# SCH_STM32F103C8T6.net
KiCad netlist of a schematic drawn in Altium Designer
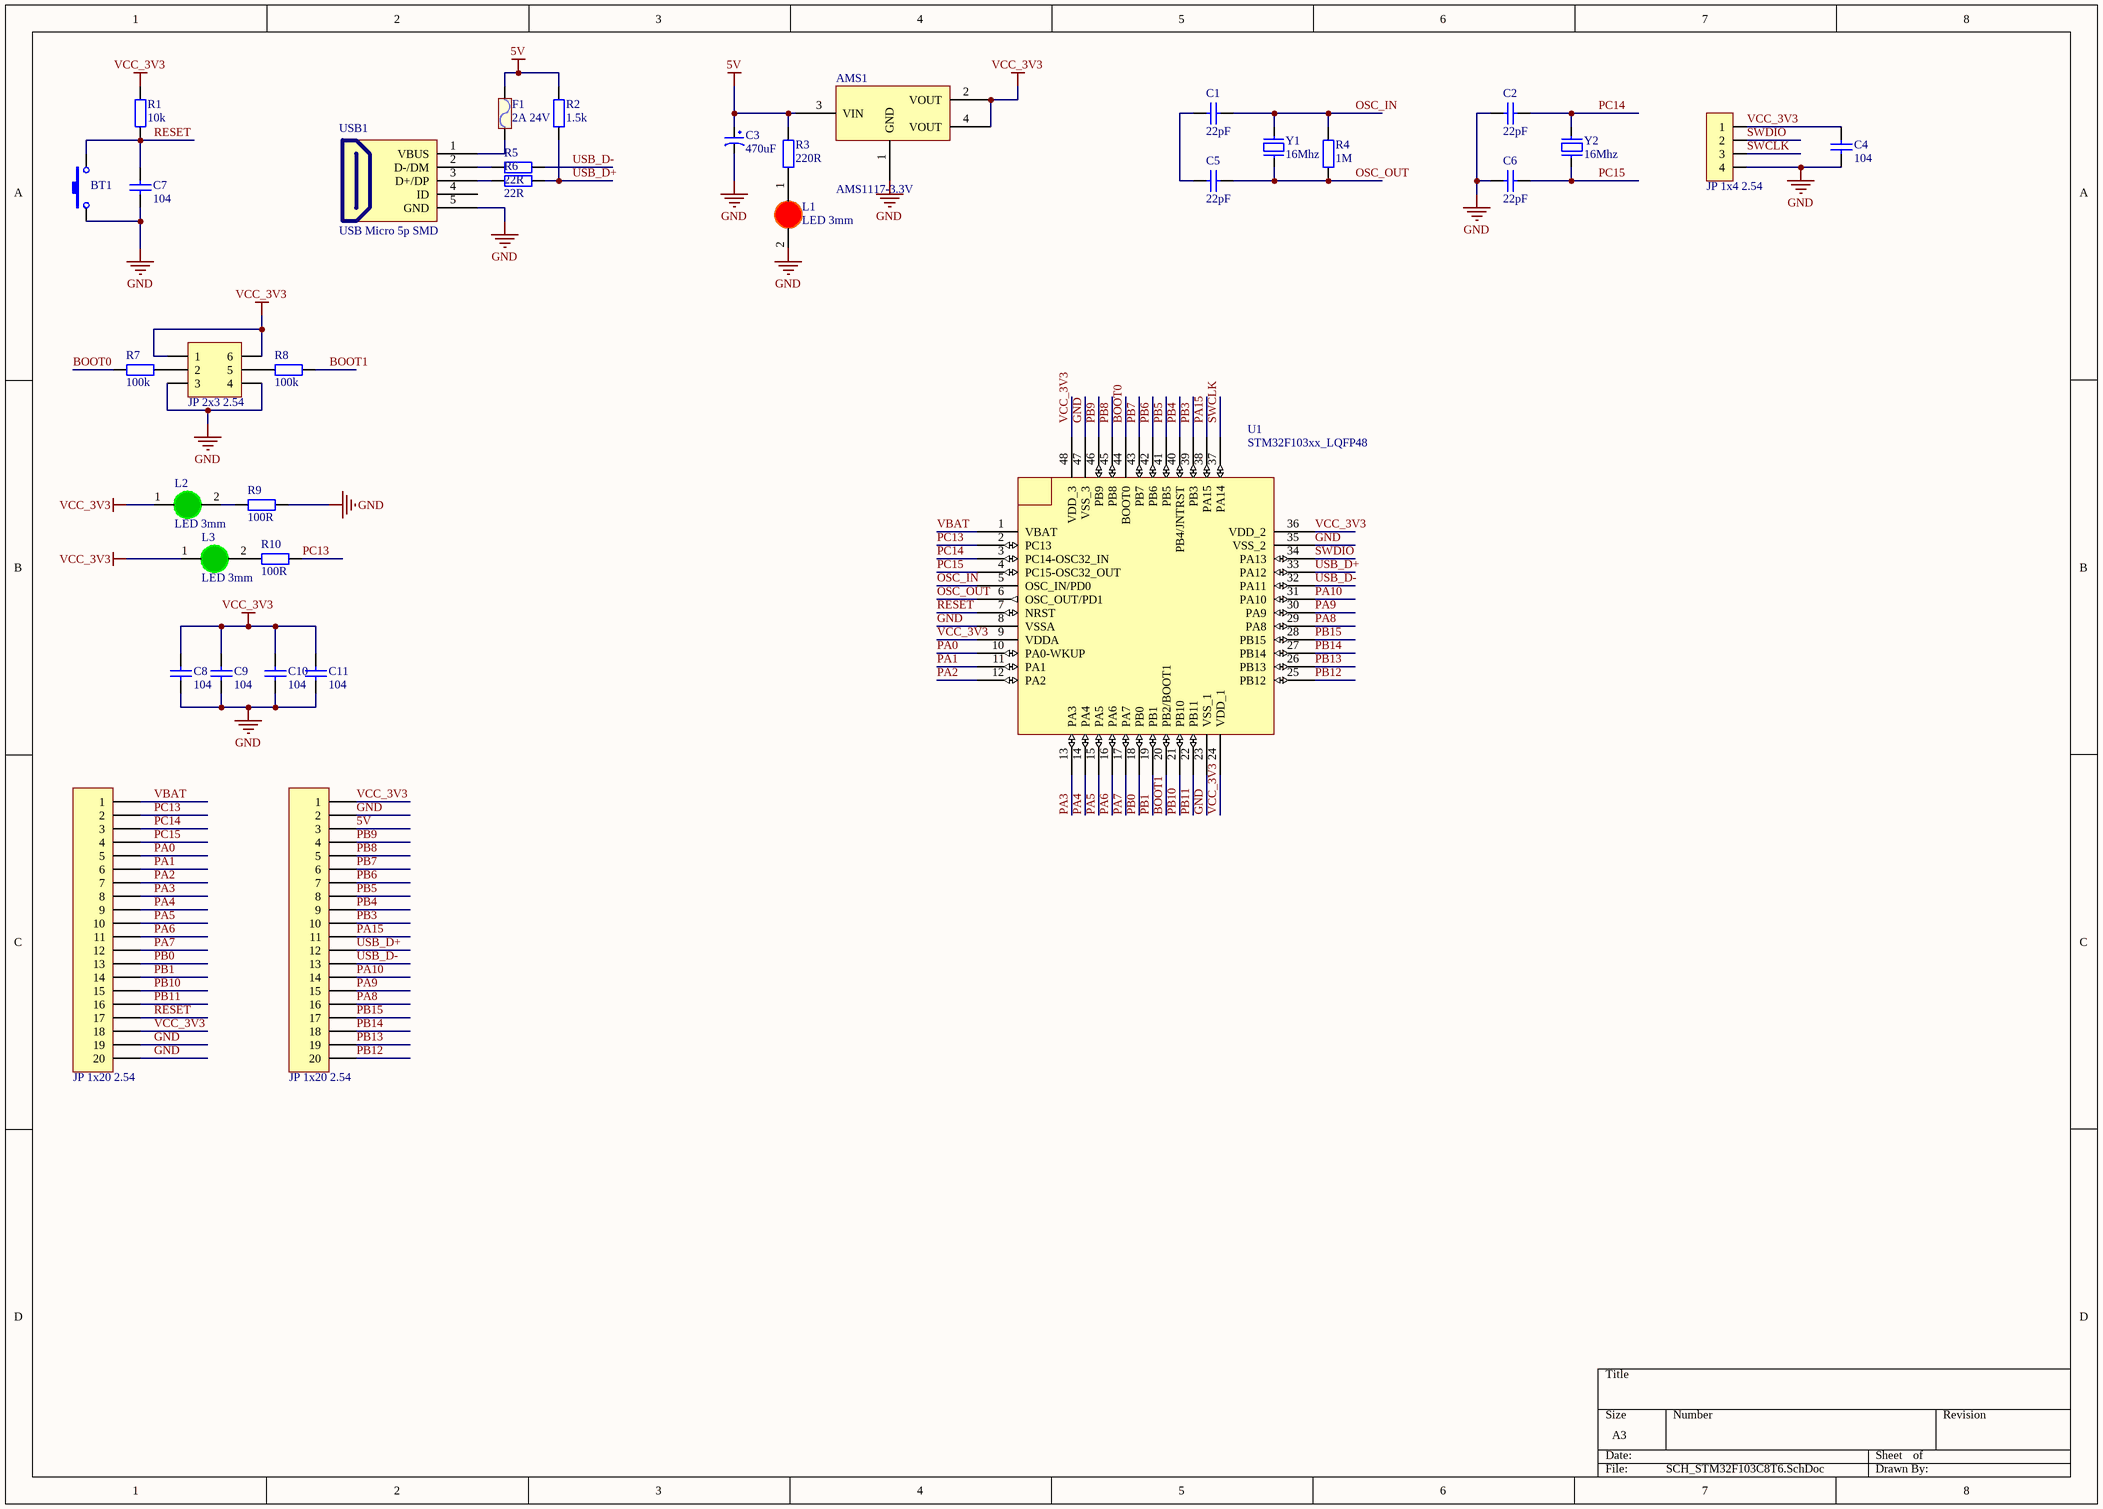
[diagram p0: SCH_STM32F103C8T6.SchDoc]

(export (version "E")
  (design (tool "Eeschema 10.0.6"))
  (components
    (comp (ref "AMS1")
      (value "AMS1117-3.3V")
      (footprint "SOT223")
      (description "Dán")
      (libsource (lib "Altium_Lib_by_KhueNguyenCreator") (part "AMS1117 SMD"))
    )
    (comp (ref "BT1")
      (value "Nut Nhan 2 Chan SMD 3x6x2.5")
      (footprint "Nut Nhan 2 Chan SMD 3x6x2.5")
      (libsource (lib "Altium_Lib_by_KhueNguyenCreator") (part "Nut Nhan 2 Chan SMD 3x6x2.5"))
    )
    (comp (ref "C1")
      (value "22pF")
      (footprint "tu 0805")
      (description "Dán")
      (libsource (lib "Altium_Lib_by_KhueNguyenCreator") (part "Tu 0805 22pF 50V 10%"))
    )
    (comp (ref "C2")
      (value "22pF")
      (footprint "tu 0805")
      (description "Dán")
      (libsource (lib "Altium_Lib_by_KhueNguyenCreator") (part "Tu 0805 22pF 50V 10%"))
    )
    (comp (ref "C3")
      (value "470uF")
      (footprint "tu hoa 8mm")
      (description "Cắm")
      (libsource (lib "Altium_Lib_by_KhueNguyenCreator") (part "Tu Hoa 470uF 16V 8x11"))
    )
    (comp (ref "C4")
      (value "104")
      (footprint "tu gom")
      (description "Cắm")
      (libsource (lib "Altium_Lib_by_KhueNguyenCreator") (part "Tu gom 104 50V"))
    )
    (comp (ref "C5")
      (value "22pF")
      (footprint "tu 0805")
      (description "Dán")
      (libsource (lib "Altium_Lib_by_KhueNguyenCreator") (part "Tu 0805 22pF 50V 10%"))
    )
    (comp (ref "C6")
      (value "22pF")
      (footprint "tu 0805")
      (description "Dán")
      (libsource (lib "Altium_Lib_by_KhueNguyenCreator") (part "Tu 0805 22pF 50V 10%"))
    )
    (comp (ref "C7")
      (value "104")
      (footprint "tu 0805")
      (description "Dán")
      (libsource (lib "Altium_Lib_by_KhueNguyenCreator") (part "Tu 0805 104 50V 10%"))
    )
    (comp (ref "C8")
      (value "104")
      (footprint "tu 0805")
      (description "Dán")
      (libsource (lib "Altium_Lib_by_KhueNguyenCreator") (part "Tu 0805 104 50V 10%"))
    )
    (comp (ref "C9")
      (value "104")
      (footprint "tu 0805")
      (description "Dán")
      (libsource (lib "Altium_Lib_by_KhueNguyenCreator") (part "Tu 0805 104 50V 10%"))
    )
    (comp (ref "C10")
      (value "104")
      (footprint "tu 0805")
      (description "Dán")
      (libsource (lib "Altium_Lib_by_KhueNguyenCreator") (part "Tu 0805 104 50V 10%"))
    )
    (comp (ref "C11")
      (value "104")
      (footprint "tu 0805")
      (description "Dán")
      (libsource (lib "Altium_Lib_by_KhueNguyenCreator") (part "Tu 0805 104 50V 10%"))
    )
    (comp (ref "F1")
      (value "2A 24V")
      (footprint "Cau chi tu phuc hoi 2A 24V SMD1812")
      (description "2A 24V SMD1812")
      (libsource (lib "Altium_Lib_by_KhueNguyenCreator") (part "Cau chi tu phuc hoi 2A 24V SMD1812"))
    )
    (comp (ref "JP1")
      (value "JP 1x4 2.54")
      (footprint "JP 1x4 DC")
      (description "Cắm")
      (libsource (lib "Altium_Lib_by_KhueNguyenCreator") (part "JP 1x4 2.54 Duc Cong"))
    )
    (comp (ref "JP2")
      (value "JP 2x3 2.54")
      (footprint "JP 2x3 DT")
      (description "Cắm")
      (libsource (lib "Altium_Lib_by_KhueNguyenCreator") (part "JP 2x3 2.54 Duc Thang"))
    )
    (comp (ref "JP3")
      (value "JP 1x20 2.54")
      (footprint "JP 1x20 DT")
      (description "Cắm")
      (libsource (lib "Altium_Lib_by_KhueNguyenCreator") (part "JP 1x20 2.54 Duc Thang"))
    )
    (comp (ref "JP4")
      (value "JP 1x20 2.54")
      (footprint "JP 1x20 DT")
      (description "Cắm")
      (libsource (lib "Altium_Lib_by_KhueNguyenCreator") (part "JP 1x20 2.54 Duc Thang"))
    )
    (comp (ref "L1")
      (value "LED 3mm")
      (footprint "LED-3MM-RED")
      (description "Cắm")
      (libsource (lib "Altium_Lib_by_KhueNguyenCreator") (part "LED 3mm Do"))
    )
    (comp (ref "L2")
      (value "LED 3mm")
      (footprint "LED-3MM-GREEN")
      (description "Cắm")
      (libsource (lib "Altium_Lib_by_KhueNguyenCreator") (part "LED 3mm Xanh La"))
    )
    (comp (ref "L3")
      (value "LED 3mm")
      (footprint "LED-3MM-GREEN")
      (description "Cắm")
      (libsource (lib "Altium_Lib_by_KhueNguyenCreator") (part "LED 3mm Xanh La"))
    )
    (comp (ref "R1")
      (value "10k")
      (footprint "tro smd 0805")
      (description "Dán")
      (libsource (lib "Altium_Lib_by_KhueNguyenCreator") (part "Tro 0805 1% 10k"))
    )
    (comp (ref "R2")
      (value "1.5k")
      (footprint "tro smd 0805")
      (description "Dán")
      (libsource (lib "Altium_Lib_by_KhueNguyenCreator") (part "Tro 0805 5% 1.5k"))
    )
    (comp (ref "R3")
      (value "220R")
      (footprint "tro smd 0805")
      (description "Dán")
      (libsource (lib "Altium_Lib_by_KhueNguyenCreator") (part "Tro 0805 5% 220R"))
    )
    (comp (ref "R4")
      (value "1M")
      (footprint "tro smd 0805")
      (description "Dán")
      (libsource (lib "Altium_Lib_by_KhueNguyenCreator") (part "Tro 0805 5% 1M"))
    )
    (comp (ref "R5")
      (value "22R")
      (footprint "tro smd 0805")
      (description "Dán")
      (libsource (lib "Altium_Lib_by_KhueNguyenCreator") (part "Tro 0805 5% 22R"))
    )
    (comp (ref "R6")
      (value "22R")
      (footprint "tro smd 0805")
      (description "Dán")
      (libsource (lib "Altium_Lib_by_KhueNguyenCreator") (part "Tro 0805 5% 22R"))
    )
    (comp (ref "R7")
      (value "100k")
      (footprint "tro smd 0603")
      (description "Dán")
      (libsource (lib "Altium_Lib_by_KhueNguyenCreator") (part "Tro 0603 5% 100k"))
    )
    (comp (ref "R8")
      (value "100k")
      (footprint "tro smd 0603")
      (description "Dán")
      (libsource (lib "Altium_Lib_by_KhueNguyenCreator") (part "Tro 0603 5% 100k"))
    )
    (comp (ref "R9")
      (value "100R")
      (footprint "tro smd 0805")
      (description "Dán")
      (libsource (lib "Altium_Lib_by_KhueNguyenCreator") (part "Tro 0805 5% 100R"))
    )
    (comp (ref "R10")
      (value "100R")
      (footprint "tro smd 0805")
      (description "Dán")
      (libsource (lib "Altium_Lib_by_KhueNguyenCreator") (part "Tro 0805 5% 100R"))
    )
    (comp (ref "U1")
      (value "STM32F103xx_LQFP48")
      (footprint "STM32_LQPF48")
      (fields (field (name "PUBLISHER") "Altium Limited"))
      (libsource (lib "Altium_Lib_by_KhueNguyenCreator") (part "STM32F103xx_LQFP48"))
    )
    (comp (ref "USB1")
      (value "USB Micro 5p SMD")
      (footprint "USB Micro 5p SMD")
      (description "USB Type B")
      (libsource (lib "Altium_Lib_by_KhueNguyenCreator") (part "USB Micro 5p SMD"))
    )
    (comp (ref "Y1")
      (value "16Mhz")
      (footprint "Thach Anh 2 chan cam")
      (description "Crystal For all Crystal 2pin.")
      (libsource (lib "Altium_Lib_by_KhueNguyenCreator") (part "Thach Anh 2 chan Cam"))
    )
    (comp (ref "Y2")
      (value "16Mhz")
      (footprint "Thach Anh 2 Chan 32,768 KHz")
      (description "Crystal For all Crystal 2pin.")
      (libsource (lib "Altium_Lib_by_KhueNguyenCreator") (part "Thach Anh 2 chan 32,768 Khz"))
    )
  )
  (nets
    (net (code "1") (name "/BOOT0") (class "Default")
      (node (ref "R7") (pin "1") (pinfunction "1_1") (pintype "passive"))
      (node (ref "U1") (pin "44") (pinfunction "BOOT0_44") (pintype "passive"))
    )
    (net (code "2") (name "/BOOT1") (class "Default")
      (node (ref "R8") (pin "2") (pinfunction "2_2") (pintype "passive"))
      (node (ref "U1") (pin "20") (pinfunction "PB2/BOOT1_20") (pintype "bidirectional"))
    )
    (net (code "3") (name "/OSC_IN") (class "Default")
      (node (ref "C1") (pin "1") (pinfunction "1_1") (pintype "passive"))
      (node (ref "R4") (pin "2") (pinfunction "2_2") (pintype "passive"))
      (node (ref "U1") (pin "5") (pinfunction "OSC_IN/PD0_5") (pintype "passive"))
      (node (ref "Y1") (pin "1") (pinfunction "1_1") (pintype "passive"))
    )
    (net (code "4") (name "/OSC_OUT") (class "Default")
      (node (ref "C5") (pin "1") (pinfunction "1_1") (pintype "passive"))
      (node (ref "R4") (pin "1") (pinfunction "1_1") (pintype "passive"))
      (node (ref "U1") (pin "6") (pinfunction "OSC_OUT/PD1_6") (pintype "output"))
      (node (ref "Y1") (pin "2") (pinfunction "2_2") (pintype "passive"))
    )
    (net (code "5") (name "/PA0") (class "Default")
      (node (ref "JP3") (pin "5") (pinfunction "5_5") (pintype "passive"))
      (node (ref "U1") (pin "10") (pinfunction "PA0-WKUP_10") (pintype "bidirectional"))
    )
    (net (code "6") (name "/PA1") (class "Default")
      (node (ref "JP3") (pin "6") (pinfunction "6_6") (pintype "passive"))
      (node (ref "U1") (pin "11") (pinfunction "PA1_11") (pintype "bidirectional"))
    )
    (net (code "7") (name "/PA2") (class "Default")
      (node (ref "JP3") (pin "7") (pinfunction "7_7") (pintype "passive"))
      (node (ref "U1") (pin "12") (pinfunction "PA2_12") (pintype "bidirectional"))
    )
    (net (code "8") (name "/PA3") (class "Default")
      (node (ref "JP3") (pin "8") (pinfunction "8_8") (pintype "passive"))
      (node (ref "U1") (pin "13") (pinfunction "PA3_13") (pintype "bidirectional"))
    )
    (net (code "9") (name "/PA4") (class "Default")
      (node (ref "JP3") (pin "9") (pinfunction "9_9") (pintype "passive"))
      (node (ref "U1") (pin "14") (pinfunction "PA4_14") (pintype "bidirectional"))
    )
    (net (code "10") (name "/PA5") (class "Default")
      (node (ref "JP3") (pin "10") (pinfunction "10_10") (pintype "passive"))
      (node (ref "U1") (pin "15") (pinfunction "PA5_15") (pintype "bidirectional"))
    )
    (net (code "11") (name "/PA6") (class "Default")
      (node (ref "JP3") (pin "11") (pinfunction "11_11") (pintype "passive"))
      (node (ref "U1") (pin "16") (pinfunction "PA6_16") (pintype "bidirectional"))
    )
    (net (code "12") (name "/PA7") (class "Default")
      (node (ref "JP3") (pin "12") (pinfunction "12_12") (pintype "passive"))
      (node (ref "U1") (pin "17") (pinfunction "PA7_17") (pintype "bidirectional"))
    )
    (net (code "13") (name "/PA8") (class "Default")
      (node (ref "JP4") (pin "16") (pinfunction "16_16") (pintype "passive"))
      (node (ref "U1") (pin "29") (pinfunction "PA8_29") (pintype "bidirectional"))
    )
    (net (code "14") (name "/PA9") (class "Default")
      (node (ref "JP4") (pin "15") (pinfunction "15_15") (pintype "passive"))
      (node (ref "U1") (pin "30") (pinfunction "PA9_30") (pintype "bidirectional"))
    )
    (net (code "15") (name "/PA10") (class "Default")
      (node (ref "JP4") (pin "14") (pinfunction "14_14") (pintype "passive"))
      (node (ref "U1") (pin "31") (pinfunction "PA10_31") (pintype "bidirectional"))
    )
    (net (code "16") (name "/PA15") (class "Default")
      (node (ref "JP4") (pin "11") (pinfunction "11_11") (pintype "passive"))
      (node (ref "U1") (pin "38") (pinfunction "PA15_38") (pintype "bidirectional"))
    )
    (net (code "17") (name "/PB0") (class "Default")
      (node (ref "JP3") (pin "13") (pinfunction "13_13") (pintype "passive"))
      (node (ref "U1") (pin "18") (pinfunction "PB0_18") (pintype "bidirectional"))
    )
    (net (code "18") (name "/PB1") (class "Default")
      (node (ref "JP3") (pin "14") (pinfunction "14_14") (pintype "passive"))
      (node (ref "U1") (pin "19") (pinfunction "PB1_19") (pintype "bidirectional"))
    )
    (net (code "19") (name "/PB3") (class "Default")
      (node (ref "JP4") (pin "10") (pinfunction "10_10") (pintype "passive"))
      (node (ref "U1") (pin "39") (pinfunction "PB3_39") (pintype "bidirectional"))
    )
    (net (code "20") (name "/PB4") (class "Default")
      (node (ref "JP4") (pin "9") (pinfunction "9_9") (pintype "passive"))
      (node (ref "U1") (pin "40") (pinfunction "PB4/JNTRST_40") (pintype "bidirectional"))
    )
    (net (code "21") (name "/PB5") (class "Default")
      (node (ref "JP4") (pin "8") (pinfunction "8_8") (pintype "passive"))
      (node (ref "U1") (pin "41") (pinfunction "PB5_41") (pintype "bidirectional"))
    )
    (net (code "22") (name "/PB6") (class "Default")
      (node (ref "JP4") (pin "7") (pinfunction "7_7") (pintype "passive"))
      (node (ref "U1") (pin "42") (pinfunction "PB6_42") (pintype "bidirectional"))
    )
    (net (code "23") (name "/PB7") (class "Default")
      (node (ref "JP4") (pin "6") (pinfunction "6_6") (pintype "passive"))
      (node (ref "U1") (pin "43") (pinfunction "PB7_43") (pintype "bidirectional"))
    )
    (net (code "24") (name "/PB8") (class "Default")
      (node (ref "JP4") (pin "5") (pinfunction "5_5") (pintype "passive"))
      (node (ref "U1") (pin "45") (pinfunction "PB8_45") (pintype "bidirectional"))
    )
    (net (code "25") (name "/PB9") (class "Default")
      (node (ref "JP4") (pin "4") (pinfunction "4_4") (pintype "passive"))
      (node (ref "U1") (pin "46") (pinfunction "PB9_46") (pintype "bidirectional"))
    )
    (net (code "26") (name "/PB10") (class "Default")
      (node (ref "JP3") (pin "15") (pinfunction "15_15") (pintype "passive"))
      (node (ref "U1") (pin "21") (pinfunction "PB10_21") (pintype "bidirectional"))
    )
    (net (code "27") (name "/PB11") (class "Default")
      (node (ref "JP3") (pin "16") (pinfunction "16_16") (pintype "passive"))
      (node (ref "U1") (pin "22") (pinfunction "PB11_22") (pintype "bidirectional"))
    )
    (net (code "28") (name "/PB12") (class "Default")
      (node (ref "JP4") (pin "20") (pinfunction "20_20") (pintype "passive"))
      (node (ref "U1") (pin "25") (pinfunction "PB12_25") (pintype "bidirectional"))
    )
    (net (code "29") (name "/PB13") (class "Default")
      (node (ref "JP4") (pin "19") (pinfunction "19_19") (pintype "passive"))
      (node (ref "U1") (pin "26") (pinfunction "PB13_26") (pintype "bidirectional"))
    )
    (net (code "30") (name "/PB14") (class "Default")
      (node (ref "JP4") (pin "18") (pinfunction "18_18") (pintype "passive"))
      (node (ref "U1") (pin "27") (pinfunction "PB14_27") (pintype "bidirectional"))
    )
    (net (code "31") (name "/PB15") (class "Default")
      (node (ref "JP4") (pin "17") (pinfunction "17_17") (pintype "passive"))
      (node (ref "U1") (pin "28") (pinfunction "PB15_28") (pintype "bidirectional"))
    )
    (net (code "32") (name "/PC13") (class "Default")
      (node (ref "JP3") (pin "2") (pinfunction "2_2") (pintype "passive"))
      (node (ref "R10") (pin "2") (pinfunction "2_2") (pintype "passive"))
      (node (ref "U1") (pin "2") (pinfunction "PC13_2") (pintype "bidirectional"))
    )
    (net (code "33") (name "/PC14") (class "Default")
      (node (ref "C2") (pin "1") (pinfunction "1_1") (pintype "passive"))
      (node (ref "JP3") (pin "3") (pinfunction "3_3") (pintype "passive"))
      (node (ref "U1") (pin "3") (pinfunction "PC14-OSC32_IN_3") (pintype "bidirectional"))
      (node (ref "Y2") (pin "2") (pinfunction "2_2") (pintype "passive"))
    )
    (net (code "34") (name "/PC15") (class "Default")
      (node (ref "C6") (pin "1") (pinfunction "1_1") (pintype "passive"))
      (node (ref "JP3") (pin "4") (pinfunction "4_4") (pintype "passive"))
      (node (ref "U1") (pin "4") (pinfunction "PC15-OSC32_OUT_4") (pintype "bidirectional"))
      (node (ref "Y2") (pin "1") (pinfunction "1_1") (pintype "passive"))
    )
    (net (code "35") (name "/RESET") (class "Default")
      (node (ref "BT1") (pin "2") (pinfunction "2_2") (pintype "passive"))
      (node (ref "C7") (pin "1") (pinfunction "1_1") (pintype "passive"))
      (node (ref "JP3") (pin "17") (pinfunction "17_17") (pintype "passive"))
      (node (ref "R1") (pin "1") (pinfunction "1_1") (pintype "passive"))
      (node (ref "U1") (pin "7") (pinfunction "NRST_7") (pintype "bidirectional"))
    )
    (net (code "36") (name "/SWCLK") (class "Default")
      (node (ref "JP1") (pin "3") (pinfunction "3_3") (pintype "passive"))
      (node (ref "U1") (pin "37") (pinfunction "PA14_37") (pintype "bidirectional"))
    )
    (net (code "37") (name "/SWDIO") (class "Default")
      (node (ref "JP1") (pin "2") (pinfunction "2_2") (pintype "passive"))
      (node (ref "U1") (pin "34") (pinfunction "PA13_34") (pintype "bidirectional"))
    )
    (net (code "38") (name "/USB_D+") (class "Default")
      (node (ref "JP4") (pin "12") (pinfunction "12_12") (pintype "passive"))
      (node (ref "R2") (pin "1") (pinfunction "1_1") (pintype "passive"))
      (node (ref "R6") (pin "2") (pinfunction "2_2") (pintype "passive"))
      (node (ref "U1") (pin "33") (pinfunction "PA12_33") (pintype "bidirectional"))
    )
    (net (code "39") (name "/USB_D-") (class "Default")
      (node (ref "JP4") (pin "13") (pinfunction "13_13") (pintype "passive"))
      (node (ref "R5") (pin "2") (pinfunction "2_2") (pintype "passive"))
      (node (ref "U1") (pin "32") (pinfunction "PA11_32") (pintype "bidirectional"))
    )
    (net (code "40") (name "/VBAT") (class "Default")
      (node (ref "JP3") (pin "1") (pinfunction "1_1") (pintype "passive"))
      (node (ref "U1") (pin "1") (pinfunction "VBAT_1") (pintype "power_in"))
    )
    (net (code "41") (name "5V") (class "Default")
      (node (ref "AMS1") (pin "3") (pinfunction "VIN_3") (pintype "passive"))
      (node (ref "C3") (pin "1") (pinfunction "1_1") (pintype "passive"))
      (node (ref "F1") (pin "2") (pinfunction "2_2") (pintype "passive"))
      (node (ref "JP4") (pin "3") (pinfunction "3_3") (pintype "passive"))
      (node (ref "R2") (pin "2") (pinfunction "2_2") (pintype "passive"))
      (node (ref "R3") (pin "2") (pinfunction "2_2") (pintype "passive"))
    )
    (net (code "42") (name "GND") (class "Default")
      (node (ref "AMS1") (pin "1") (pinfunction "GND_1") (pintype "passive"))
      (node (ref "BT1") (pin "1") (pinfunction "1_1") (pintype "passive"))
      (node (ref "C10") (pin "2") (pinfunction "2_2") (pintype "passive"))
      (node (ref "C11") (pin "2") (pinfunction "2_2") (pintype "passive"))
      (node (ref "C2") (pin "2") (pinfunction "2_2") (pintype "passive"))
      (node (ref "C3") (pin "2") (pinfunction "2_2") (pintype "passive"))
      (node (ref "C4") (pin "2") (pinfunction "2_2") (pintype "passive"))
      (node (ref "C6") (pin "2") (pinfunction "2_2") (pintype "passive"))
      (node (ref "C7") (pin "2") (pinfunction "2_2") (pintype "passive"))
      (node (ref "C8") (pin "2") (pinfunction "2_2") (pintype "passive"))
      (node (ref "C9") (pin "2") (pinfunction "2_2") (pintype "passive"))
      (node (ref "JP1") (pin "4") (pinfunction "4_4") (pintype "passive"))
      (node (ref "JP2") (pin "3") (pinfunction "3_3") (pintype "passive"))
      (node (ref "JP2") (pin "4") (pinfunction "4_4") (pintype "passive"))
      (node (ref "JP3") (pin "19") (pinfunction "19_19") (pintype "passive"))
      (node (ref "JP3") (pin "20") (pinfunction "20_20") (pintype "passive"))
      (node (ref "JP4") (pin "2") (pinfunction "2_2") (pintype "passive"))
      (node (ref "L1") (pin "2") (pinfunction "K_2") (pintype "passive"))
      (node (ref "R9") (pin "2") (pinfunction "2_2") (pintype "passive"))
      (node (ref "U1") (pin "23") (pinfunction "VSS_1_23") (pintype "power_in"))
      (node (ref "U1") (pin "35") (pinfunction "VSS_2_35") (pintype "power_in"))
      (node (ref "U1") (pin "47") (pinfunction "VSS_3_47") (pintype "power_in"))
      (node (ref "U1") (pin "8") (pinfunction "VSSA_8") (pintype "power_in"))
      (node (ref "USB1") (pin "5") (pinfunction "GND_5") (pintype "passive"))
    )
    (net (code "43") (name "Net-(C1-Pad2)") (class "Default")
      (node (ref "C1") (pin "2") (pinfunction "2_2") (pintype "passive"))
      (node (ref "C5") (pin "2") (pinfunction "2_2") (pintype "passive"))
    )
    (net (code "44") (name "Net-(JP2-Pad2)") (class "Default")
      (node (ref "JP2") (pin "2") (pinfunction "2_2") (pintype "passive"))
      (node (ref "R7") (pin "2") (pinfunction "2_2") (pintype "passive"))
    )
    (net (code "45") (name "Net-(JP2-Pad5)") (class "Default")
      (node (ref "JP2") (pin "5") (pinfunction "5_5") (pintype "passive"))
      (node (ref "R8") (pin "1") (pinfunction "1_1") (pintype "passive"))
    )
    (net (code "46") (name "Net-(L1-A)") (class "Default")
      (node (ref "L1") (pin "1") (pinfunction "A_1") (pintype "passive"))
      (node (ref "R3") (pin "1") (pinfunction "1_1") (pintype "passive"))
    )
    (net (code "47") (name "Net-(L2-K)") (class "Default")
      (node (ref "L2") (pin "2") (pinfunction "K_2") (pintype "passive"))
      (node (ref "R9") (pin "1") (pinfunction "1_1") (pintype "passive"))
    )
    (net (code "48") (name "Net-(L3-K)") (class "Default")
      (node (ref "L3") (pin "2") (pinfunction "K_2") (pintype "passive"))
      (node (ref "R10") (pin "1") (pinfunction "1_1") (pintype "passive"))
    )
    (net (code "49") (name "Net-(USB1-D+{slash}DP)") (class "Default")
      (node (ref "R6") (pin "1") (pinfunction "1_1") (pintype "passive"))
      (node (ref "USB1") (pin "3") (pinfunction "D+/DP_3") (pintype "passive"))
    )
    (net (code "50") (name "Net-(USB1-D-{slash}DM)") (class "Default")
      (node (ref "R5") (pin "1") (pinfunction "1_1") (pintype "passive"))
      (node (ref "USB1") (pin "2") (pinfunction "D-/DM_2") (pintype "passive"))
    )
    (net (code "51") (name "Net-(USB1-VBUS)") (class "Default")
      (node (ref "F1") (pin "1") (pinfunction "1_1") (pintype "passive"))
      (node (ref "USB1") (pin "1") (pinfunction "VBUS_1") (pintype "passive"))
    )
    (net (code "52") (name "VCC_3V3") (class "Default")
      (node (ref "AMS1") (pin "2") (pinfunction "VOUT_2") (pintype "passive"))
      (node (ref "AMS1") (pin "4") (pinfunction "VOUT_4") (pintype "passive"))
      (node (ref "C10") (pin "1") (pinfunction "1_1") (pintype "passive"))
      (node (ref "C11") (pin "1") (pinfunction "1_1") (pintype "passive"))
      (node (ref "C4") (pin "1") (pinfunction "1_1") (pintype "passive"))
      (node (ref "C8") (pin "1") (pinfunction "1_1") (pintype "passive"))
      (node (ref "C9") (pin "1") (pinfunction "1_1") (pintype "passive"))
      (node (ref "JP1") (pin "1") (pinfunction "1_1") (pintype "passive"))
      (node (ref "JP2") (pin "1") (pinfunction "1_1") (pintype "passive"))
      (node (ref "JP2") (pin "6") (pinfunction "6_6") (pintype "passive"))
      (node (ref "JP3") (pin "18") (pinfunction "18_18") (pintype "passive"))
      (node (ref "JP4") (pin "1") (pinfunction "1_1") (pintype "passive"))
      (node (ref "L2") (pin "1") (pinfunction "A_1") (pintype "passive"))
      (node (ref "L3") (pin "1") (pinfunction "A_1") (pintype "passive"))
      (node (ref "R1") (pin "2") (pinfunction "2_2") (pintype "passive"))
      (node (ref "U1") (pin "24") (pinfunction "VDD_1_24") (pintype "power_in"))
      (node (ref "U1") (pin "36") (pinfunction "VDD_2_36") (pintype "power_in"))
      (node (ref "U1") (pin "48") (pinfunction "VDD_3_48") (pintype "power_in"))
      (node (ref "U1") (pin "9") (pinfunction "VDDA_9") (pintype "power_in"))
    )
    (net (code "53") (name "unconnected-(USB1-ID-Pad4)") (class "Default")
      (node (ref "USB1") (pin "4") (pinfunction "ID_4") (pintype "passive"))
    )
  )
)
